# blockoccdelay.net
KiCad netlist of a schematic drawn in EAGLE
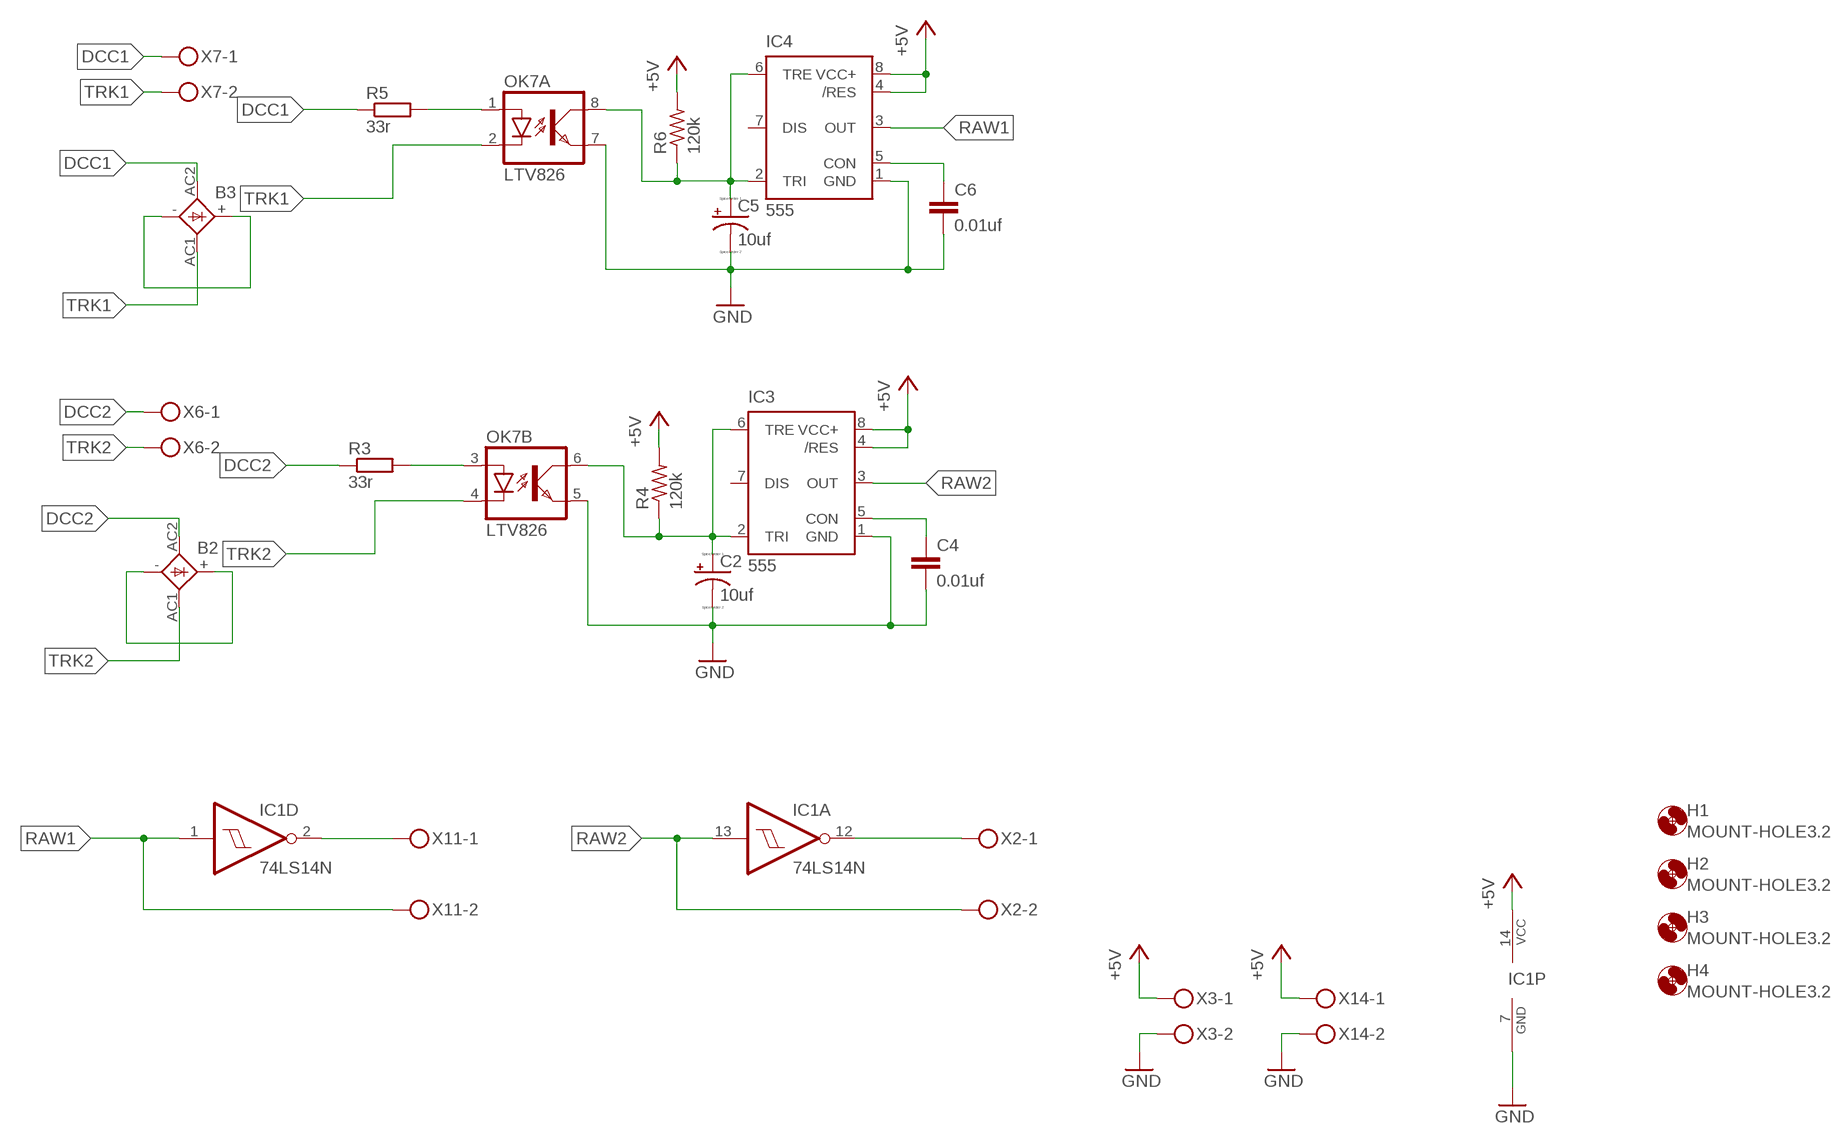
[diagram p0: schematic, sheet 1]

(export (version "E")
  (design (tool "Eeschema 10.0.6"))
  (components
    (comp (ref "B2")
      (value "GBU4")
      (footprint "eagle-import:GBU4S")
      (libsource (lib "eagle-import") (part "GBU4"))
    )
    (comp (ref "B3")
      (value "GBU4")
      (footprint "eagle-import:GBU4S")
      (libsource (lib "eagle-import") (part "GBU4"))
    )
    (comp (ref "C2")
      (value "10uf")
      (footprint "eagle-import:E2,5-6")
      (libsource (lib "eagle-import") (part "CPOL-USE2.5-6"))
    )
    (comp (ref "C4")
      (value "0.01uf")
      (footprint "eagle-import:C050-035X075")
      (libsource (lib "eagle-import") (part "C-EU050-035X075"))
    )
    (comp (ref "C5")
      (value "10uf")
      (footprint "eagle-import:E2,5-6")
      (libsource (lib "eagle-import") (part "CPOL-USE2.5-6"))
    )
    (comp (ref "C6")
      (value "0.01uf")
      (footprint "eagle-import:C050-035X075")
      (libsource (lib "eagle-import") (part "C-EU050-035X075"))
    )
    (comp (ref "H1")
      (value "MOUNT-HOLE3.2")
      (footprint "eagle-import:3,2")
      (libsource (lib "eagle-import") (part "MOUNT-HOLE3.2"))
    )
    (comp (ref "H2")
      (value "MOUNT-HOLE3.2")
      (footprint "eagle-import:3,2")
      (libsource (lib "eagle-import") (part "MOUNT-HOLE3.2"))
    )
    (comp (ref "H3")
      (value "MOUNT-HOLE3.2")
      (footprint "eagle-import:3,2")
      (libsource (lib "eagle-import") (part "MOUNT-HOLE3.2"))
    )
    (comp (ref "H4")
      (value "MOUNT-HOLE3.2")
      (footprint "eagle-import:3,2")
      (libsource (lib "eagle-import") (part "MOUNT-HOLE3.2"))
    )
    (comp (ref "IC1")
      (value "74LS14N")
      (footprint "eagle-import:DIL14")
      (libsource (lib "eagle-import") (part "7414NLS"))
    )
    (comp (ref "IC3")
      (value "555")
      (footprint "eagle-import:DIP08")
      (libsource (lib "eagle-import") (part "555P"))
    )
    (comp (ref "IC4")
      (value "555")
      (footprint "eagle-import:DIP08")
      (libsource (lib "eagle-import") (part "555P"))
    )
    (comp (ref "OK7")
      (value "LTV826")
      (footprint "eagle-import:DIL08")
      (libsource (lib "eagle-import") (part "LTV826"))
    )
    (comp (ref "R3")
      (value "33r")
      (footprint "eagle-import:0207_2V")
      (libsource (lib "eagle-import") (part "R-EU_0207/2V"))
    )
    (comp (ref "R4")
      (value "120k")
      (footprint "eagle-import:0309V")
      (libsource (lib "eagle-import") (part "R-US_0309/V"))
    )
    (comp (ref "R5")
      (value "33r")
      (footprint "eagle-import:0207_2V")
      (libsource (lib "eagle-import") (part "R-EU_0207/2V"))
    )
    (comp (ref "R6")
      (value "120k")
      (footprint "eagle-import:0309V")
      (libsource (lib "eagle-import") (part "R-US_0309/V"))
    )
    (comp (ref "X2")
      (value "MKDSN1,5/2-5,08")
      (footprint "eagle-import:MKDSN1,5_2-5,08")
      (libsource (lib "eagle-import") (part "MKDSN1,5/2-5,08"))
    )
    (comp (ref "X3")
      (value "MKDSN1,5/2-5,08")
      (footprint "eagle-import:MKDSN1,5_2-5,08")
      (libsource (lib "eagle-import") (part "MKDSN1,5/2-5,08"))
    )
    (comp (ref "X6")
      (value "MKDSN1,5/2-5,08")
      (footprint "eagle-import:MKDSN1,5_2-5,08")
      (libsource (lib "eagle-import") (part "MKDSN1,5/2-5,08"))
    )
    (comp (ref "X7")
      (value "MKDSN1,5/2-5,08")
      (footprint "eagle-import:MKDSN1,5_2-5,08")
      (libsource (lib "eagle-import") (part "MKDSN1,5/2-5,08"))
    )
    (comp (ref "X11")
      (value "MKDSN1,5/2-5,08")
      (footprint "eagle-import:MKDSN1,5_2-5,08")
      (libsource (lib "eagle-import") (part "MKDSN1,5/2-5,08"))
    )
    (comp (ref "X14")
      (value "MKDSN1,5/2-5,08")
      (footprint "eagle-import:MKDSN1,5_2-5,08")
      (libsource (lib "eagle-import") (part "MKDSN1,5/2-5,08"))
    )
  )
  (nets
    (net (code "1") (name "+5V") (class "Default")
      (node (ref "IC1") (pin "14") (pinfunction "VCC_14") (pintype "power_in"))
      (node (ref "IC3") (pin "4") (pinfunction "/RES_4") (pintype "input"))
      (node (ref "IC3") (pin "8") (pinfunction "VCC+_8") (pintype "power_in"))
      (node (ref "IC4") (pin "4") (pinfunction "/RES_4") (pintype "input"))
      (node (ref "IC4") (pin "8") (pinfunction "VCC+_8") (pintype "power_in"))
      (node (ref "R4") (pin "2") (pinfunction "2_2") (pintype "passive"))
      (node (ref "R6") (pin "2") (pinfunction "2_2") (pintype "passive"))
      (node (ref "X14") (pin "1") (pinfunction "KL_1") (pintype "passive"))
      (node (ref "X3") (pin "1") (pinfunction "KL_1") (pintype "passive"))
    )
    (net (code "2") (name "DCC1") (class "Default")
      (node (ref "B3") (pin "AC2") (pinfunction "AC1_AC2") (pintype "passive"))
      (node (ref "R5") (pin "1") (pinfunction "1_1") (pintype "passive"))
      (node (ref "X7") (pin "1") (pinfunction "KL_1") (pintype "passive"))
    )
    (net (code "3") (name "DCC2") (class "Default")
      (node (ref "B2") (pin "AC2") (pinfunction "AC1_AC2") (pintype "passive"))
      (node (ref "R3") (pin "1") (pinfunction "1_1") (pintype "passive"))
      (node (ref "X6") (pin "1") (pinfunction "KL_1") (pintype "passive"))
    )
    (net (code "4") (name "GND") (class "Default")
      (node (ref "C2") (pin "-") (pinfunction "-_-") (pintype "passive"))
      (node (ref "C4") (pin "2") (pinfunction "2_2") (pintype "passive"))
      (node (ref "C5") (pin "-") (pinfunction "-_-") (pintype "passive"))
      (node (ref "C6") (pin "2") (pinfunction "2_2") (pintype "passive"))
      (node (ref "IC1") (pin "7") (pinfunction "GND_7") (pintype "power_in"))
      (node (ref "IC3") (pin "1") (pinfunction "GND_1") (pintype "power_in"))
      (node (ref "IC4") (pin "1") (pinfunction "GND_1") (pintype "power_in"))
      (node (ref "OK7") (pin "5") (pinfunction "EMIT_5") (pintype "passive"))
      (node (ref "OK7") (pin "7") (pinfunction "EMIT_7") (pintype "passive"))
      (node (ref "X14") (pin "2") (pinfunction "KL_2") (pintype "passive"))
      (node (ref "X3") (pin "2") (pinfunction "KL_2") (pintype "passive"))
    )
    (net (code "5") (name "Net-(B2-Pad+)") (class "Default")
      (node (ref "B2") (pin "+") (pinfunction "+_+") (pintype "passive"))
      (node (ref "B2") (pin "-") (pinfunction "-_-") (pintype "passive"))
    )
    (net (code "6") (name "Net-(B3-Pad+)") (class "Default")
      (node (ref "B3") (pin "+") (pinfunction "+_+") (pintype "passive"))
      (node (ref "B3") (pin "-") (pinfunction "-_-") (pintype "passive"))
    )
    (net (code "7") (name "Net-(IC1A-O)") (class "Default")
      (node (ref "IC1") (pin "12") (pinfunction "O_12") (pintype "output"))
      (node (ref "X2") (pin "1") (pinfunction "KL_1") (pintype "passive"))
    )
    (net (code "8") (name "Net-(IC1D-O)") (class "Default")
      (node (ref "IC1") (pin "2") (pinfunction "O_2") (pintype "output"))
      (node (ref "X11") (pin "1") (pinfunction "KL_1") (pintype "passive"))
    )
    (net (code "9") (name "Net-(IC3-CON)") (class "Default")
      (node (ref "C4") (pin "1") (pinfunction "1_1") (pintype "passive"))
      (node (ref "IC3") (pin "5") (pinfunction "CON_5") (pintype "input"))
    )
    (net (code "10") (name "Net-(IC3-TRE)") (class "Default")
      (node (ref "C2") (pin "+") (pinfunction "+_+") (pintype "passive"))
      (node (ref "IC3") (pin "2") (pinfunction "TRI_2") (pintype "input"))
      (node (ref "IC3") (pin "6") (pinfunction "TRE_6") (pintype "input"))
      (node (ref "OK7") (pin "6") (pinfunction "COL_6") (pintype "passive"))
      (node (ref "R4") (pin "1") (pinfunction "1_1") (pintype "passive"))
    )
    (net (code "11") (name "Net-(IC4-CON)") (class "Default")
      (node (ref "C6") (pin "1") (pinfunction "1_1") (pintype "passive"))
      (node (ref "IC4") (pin "5") (pinfunction "CON_5") (pintype "input"))
    )
    (net (code "12") (name "Net-(IC4-TRE)") (class "Default")
      (node (ref "C5") (pin "+") (pinfunction "+_+") (pintype "passive"))
      (node (ref "IC4") (pin "2") (pinfunction "TRI_2") (pintype "input"))
      (node (ref "IC4") (pin "6") (pinfunction "TRE_6") (pintype "input"))
      (node (ref "OK7") (pin "8") (pinfunction "COL_8") (pintype "passive"))
      (node (ref "R6") (pin "1") (pinfunction "1_1") (pintype "passive"))
    )
    (net (code "13") (name "Net-(OK7A-A)") (class "Default")
      (node (ref "OK7") (pin "1") (pinfunction "A_1") (pintype "passive"))
      (node (ref "R5") (pin "2") (pinfunction "2_2") (pintype "passive"))
    )
    (net (code "14") (name "Net-(OK7B-A)") (class "Default")
      (node (ref "OK7") (pin "3") (pinfunction "A_3") (pintype "passive"))
      (node (ref "R3") (pin "2") (pinfunction "2_2") (pintype "passive"))
    )
    (net (code "15") (name "RAW1") (class "Default")
      (node (ref "IC1") (pin "1") (pinfunction "I_1") (pintype "input"))
      (node (ref "IC4") (pin "3") (pinfunction "OUT_3") (pintype "output"))
      (node (ref "X11") (pin "2") (pinfunction "KL_2") (pintype "passive"))
    )
    (net (code "16") (name "RAW2") (class "Default")
      (node (ref "IC1") (pin "13") (pinfunction "I_13") (pintype "input"))
      (node (ref "IC3") (pin "3") (pinfunction "OUT_3") (pintype "output"))
      (node (ref "X2") (pin "2") (pinfunction "KL_2") (pintype "passive"))
    )
    (net (code "17") (name "TRK1") (class "Default")
      (node (ref "B3") (pin "AC1") (pinfunction "AC2_AC1") (pintype "passive"))
      (node (ref "OK7") (pin "2") (pinfunction "C_2") (pintype "passive"))
      (node (ref "X7") (pin "2") (pinfunction "KL_2") (pintype "passive"))
    )
    (net (code "18") (name "TRK2") (class "Default")
      (node (ref "B2") (pin "AC1") (pinfunction "AC2_AC1") (pintype "passive"))
      (node (ref "OK7") (pin "4") (pinfunction "C_4") (pintype "passive"))
      (node (ref "X6") (pin "2") (pinfunction "KL_2") (pintype "passive"))
    )
    (net (code "19") (name "unconnected-(IC3-DIS-Pad7)") (class "Default")
      (node (ref "IC3") (pin "7") (pinfunction "DIS_7") (pintype "input"))
    )
    (net (code "20") (name "unconnected-(IC4-DIS-Pad7)") (class "Default")
      (node (ref "IC4") (pin "7") (pinfunction "DIS_7") (pintype "input"))
    )
  )
)
